# rf_txpa.net
KiCad netlist of a schematic drawn in Altium Designer
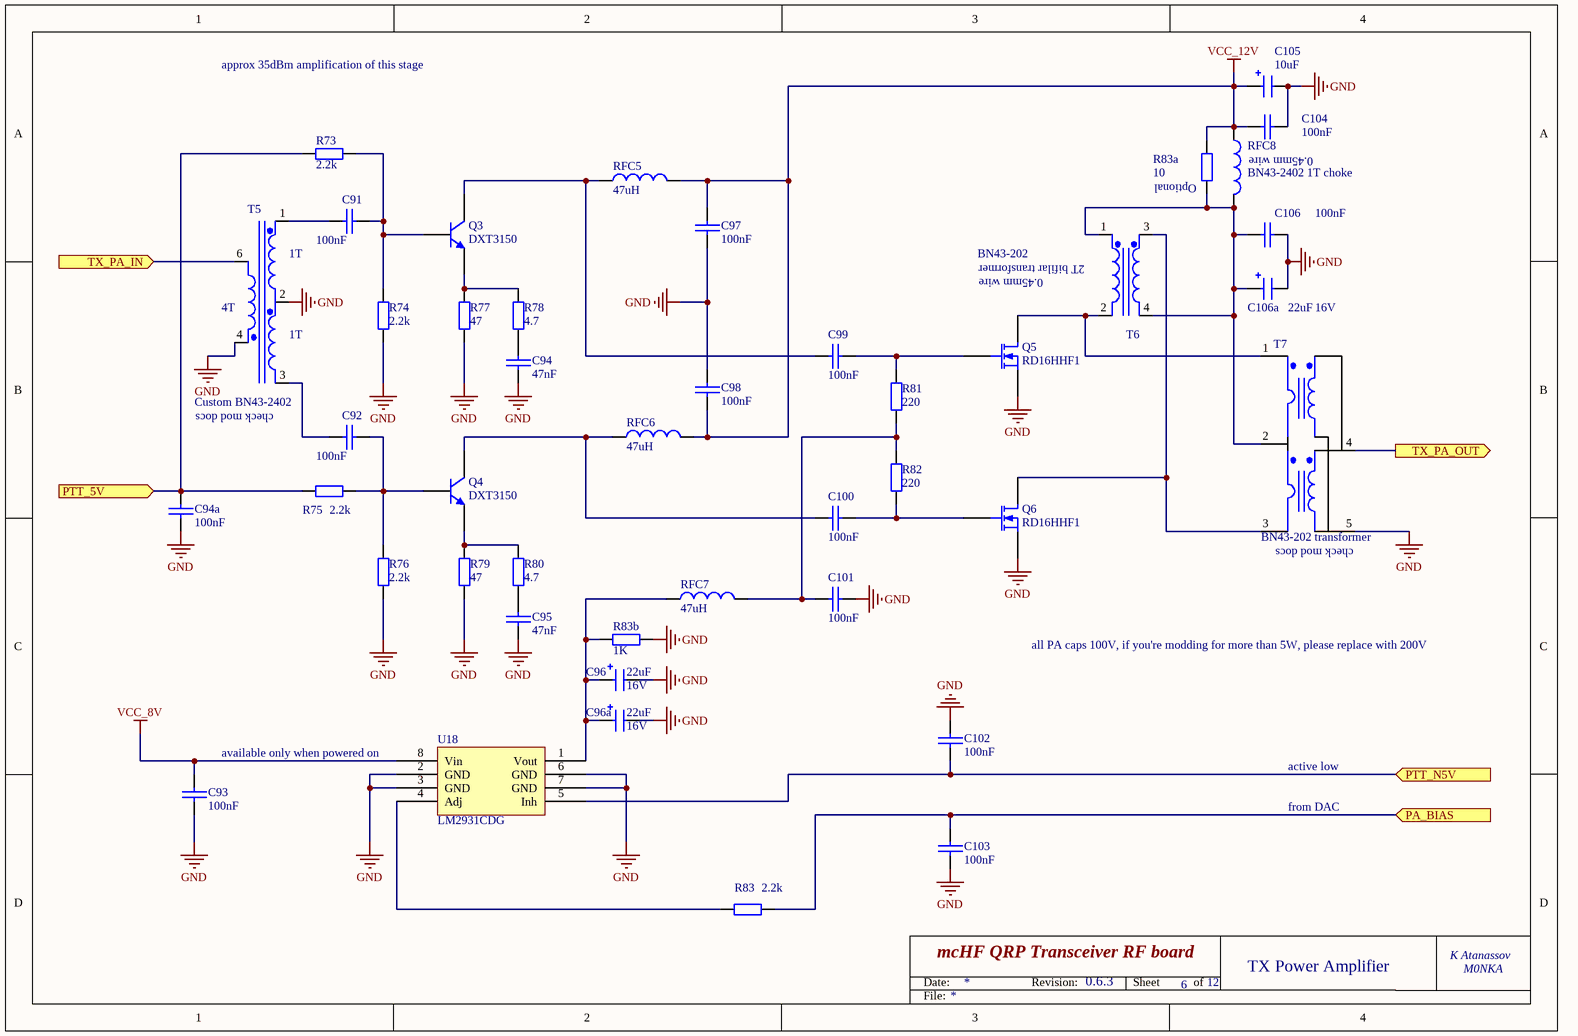
[diagram p0: rf_txpa.SchDoc]

(export (version "E")
  (design (tool "Eeschema 10.0.6"))
  (components
    (comp (ref "C91")
      (value "100nF")
      (footprint "0805-Pro")
      (description "Capacitor")
      (fields (field (name "VOLTAGE") "100V"))
      (libsource (lib "mcHF_rf") (part "CAP"))
    )
    (comp (ref "C92")
      (value "100nF")
      (footprint "0805-Pro")
      (description "Capacitor")
      (fields (field (name "VOLTAGE") "100V"))
      (libsource (lib "mcHF_rf") (part "CAP"))
    )
    (comp (ref "C93")
      (value "100nF")
      (footprint "0805-Pro")
      (description "Capacitor")
      (fields (field (name "VOLTAGE") "100V"))
      (libsource (lib "mcHF_rf") (part "CAP"))
    )
    (comp (ref "C94")
      (value "47nF")
      (footprint "0805-Pro")
      (description "Capacitor")
      (libsource (lib "mcHF_rf") (part "CAP"))
    )
    (comp (ref "C94a")
      (value "100nF")
      (footprint "0805-Pro")
      (description "Capacitor")
      (fields (field (name "VOLTAGE") "100V"))
      (libsource (lib "mcHF_rf") (part "CAP"))
    )
    (comp (ref "C95")
      (value "47nF")
      (footprint "0805-Pro")
      (description "Capacitor")
      (libsource (lib "mcHF_rf") (part "CAP"))
    )
    (comp (ref "C96")
      (value "22uF")
      (footprint "1206_Elec_Cap_N")
      (description "Electrolitic capacitor")
      (fields (field (name "VOLTAGE") "16V"))
      (libsource (lib "mcHF_rf") (part "CAP-POL"))
    )
    (comp (ref "C96a")
      (value "22uF")
      (footprint "1206_Elec_Cap_N")
      (description "Electrolitic capacitor")
      (fields (field (name "VOLTAGE") "16V"))
      (libsource (lib "mcHF_rf") (part "CAP-POL"))
    )
    (comp (ref "C97")
      (value "100nF")
      (footprint "0805-Pro")
      (description "Capacitor")
      (fields (field (name "VOLTAGE") "100V"))
      (libsource (lib "mcHF_rf") (part "CAP"))
    )
    (comp (ref "C98")
      (value "100nF")
      (footprint "0805-Pro")
      (description "Capacitor")
      (fields (field (name "VOLTAGE") "100V"))
      (libsource (lib "mcHF_rf") (part "CAP"))
    )
    (comp (ref "C99")
      (value "100nF")
      (footprint "0805-Pro")
      (description "Capacitor")
      (fields (field (name "VOLTAGE") "100V"))
      (libsource (lib "mcHF_rf") (part "CAP"))
    )
    (comp (ref "C100")
      (value "100nF")
      (footprint "0805-Pro")
      (description "Capacitor")
      (fields (field (name "VOLTAGE") "100V"))
      (libsource (lib "mcHF_rf") (part "CAP"))
    )
    (comp (ref "C101")
      (value "100nF")
      (footprint "0805-Pro")
      (description "Capacitor")
      (fields (field (name "VOLTAGE") "100V"))
      (libsource (lib "mcHF_rf") (part "CAP"))
    )
    (comp (ref "C102")
      (value "100nF")
      (footprint "0805-Pro")
      (description "Capacitor")
      (fields (field (name "VOLTAGE") "100V"))
      (libsource (lib "mcHF_rf") (part "CAP"))
    )
    (comp (ref "C103")
      (value "100nF")
      (footprint "0805-Pro")
      (description "Capacitor")
      (fields (field (name "VOLTAGE") "100V"))
      (libsource (lib "mcHF_rf") (part "CAP"))
    )
    (comp (ref "C104")
      (value "100nF")
      (footprint "0805-Pro")
      (description "Capacitor")
      (fields (field (name "VOLTAGE") "100V"))
      (libsource (lib "mcHF_rf") (part "CAP"))
    )
    (comp (ref "C105")
      (value "10uF")
      (footprint "1206_Elec_Cap_N")
      (description "Electrolitic capacitor")
      (libsource (lib "mcHF_rf") (part "CAP-POL"))
    )
    (comp (ref "C106")
      (value "100nF")
      (footprint "0805-Pro")
      (description "Capacitor")
      (fields (field (name "VOLTAGE") "100V"))
      (libsource (lib "mcHF_rf") (part "CAP"))
    )
    (comp (ref "C106a")
      (value "22uF")
      (footprint "1206_Elec_Cap_N")
      (description "Electrolitic capacitor")
      (fields (field (name "VOLTAGE") "16V"))
      (libsource (lib "mcHF_rf") (part "CAP-POL"))
    )
    (comp (ref "Q3")
      (value "DXT3150")
      (footprint "SOT89L_new")
      (description "BIPOLAR, TRANSISTOR, NPN, SOT-89")
      (libsource (lib "mcHF_rf") (part "DXT3150"))
    )
    (comp (ref "Q4")
      (value "DXT3150")
      (footprint "SOT89L_new")
      (description "BIPOLAR, TRANSISTOR, NPN, SOT-89")
      (libsource (lib "mcHF_rf") (part "DXT3150"))
    )
    (comp (ref "Q5")
      (value "RD16HHF1")
      (footprint "TO-220RF_dual")
      (description "Silicon RF Power MOS FET")
      (libsource (lib "mcHF_rf") (part "RD16HHF1"))
    )
    (comp (ref "Q6")
      (value "RD16HHF1")
      (footprint "TO-220RF_dual")
      (description "Silicon RF Power MOS FET")
      (libsource (lib "mcHF_rf") (part "RD16HHF1"))
    )
    (comp (ref "R73")
      (value "2.2k")
      (footprint "0805-Pro")
      (description "Resistor")
      (libsource (lib "") (part "RES_1"))
    )
    (comp (ref "R74")
      (value "2.2k")
      (footprint "0805-Pro")
      (description "Resistor")
      (libsource (lib "mcHF_rf") (part "RES"))
    )
    (comp (ref "R75")
      (value "2.2k")
      (footprint "0805-Pro")
      (description "Resistor")
      (libsource (lib "") (part "RES_3"))
    )
    (comp (ref "R76")
      (value "2.2k")
      (footprint "0805-Pro")
      (description "Resistor")
      (libsource (lib "mcHF_rf") (part "RES"))
    )
    (comp (ref "R77")
      (value "47")
      (footprint "0805-Pro")
      (description "Resistor")
      (libsource (lib "") (part "RES_2"))
    )
    (comp (ref "R78")
      (value "4.7")
      (footprint "0805-Pro")
      (description "Resistor")
      (libsource (lib "") (part "RES_2"))
    )
    (comp (ref "R79")
      (value "47")
      (footprint "0805-Pro")
      (description "Resistor")
      (libsource (lib "") (part "RES_2"))
    )
    (comp (ref "R80")
      (value "4.7")
      (footprint "0805-Pro")
      (description "Resistor")
      (libsource (lib "") (part "RES_2"))
    )
    (comp (ref "R81")
      (value "220")
      (footprint "0805-Pro")
      (description "Resistor")
      (libsource (lib "") (part "RES_2"))
    )
    (comp (ref "R82")
      (value "220")
      (footprint "0805-Pro")
      (description "Resistor")
      (libsource (lib "") (part "RES_2"))
    )
    (comp (ref "R83")
      (value "2.2k")
      (footprint "0805-Pro")
      (description "Resistor")
      (libsource (lib "") (part "RES_3"))
    )
    (comp (ref "R83a")
      (value "10")
      (footprint "0805-Pro")
      (description "Resistor")
      (libsource (lib "") (part "RES_2"))
    )
    (comp (ref "R83b")
      (value "1K")
      (footprint "0805-Pro")
      (description "Resistor")
      (libsource (lib "") (part "RES_1"))
    )
    (comp (ref "RFC5")
      (value "47uH")
      (footprint "0805-Pro")
      (description "INDUCTOR, SIGNAL LINE, 4.7UH, 1005")
      (libsource (lib "mcHF_rf") (part "TDK-NLV25T"))
    )
    (comp (ref "RFC6")
      (value "47uH")
      (footprint "0805-Pro")
      (description "INDUCTOR, SIGNAL LINE, 4.7UH, 1005")
      (libsource (lib "mcHF_rf") (part "TDK-NLV25T"))
    )
    (comp (ref "RFC7")
      (value "47uH")
      (footprint "0805-Pro")
      (description "INDUCTOR, SIGNAL LINE, 4.7UH, 1005")
      (libsource (lib "mcHF_rf") (part "TDK-NLV25T"))
    )
    (comp (ref "RFC8")
      (value "BN43-2402 1T choke")
      (footprint "F_Bead")
      (description "BN43-2402 1t choke")
      (libsource (lib "mcHF_rf") (part "FER_BEAD"))
    )
    (comp (ref "T5")
      (value "Custom BN43-2402")
      (footprint "SOP5_NEW1thr")
      (description "Transformer 4:1")
      (libsource (lib "mcHF_rf") (part "CX2074NL"))
    )
    (comp (ref "T6")
      (value "BN43-202")
      (footprint "PA_TRM_b1")
      (description "BN43-202 bifilar transformer")
      (libsource (lib "mcHF_rf") (part "PA_TR_b"))
    )
    (comp (ref "T7")
      (value "BN43-202 transformer")
      (footprint "PA_TRM_4m")
      (description "BN43-202 2:3 transformer")
      (libsource (lib "mcHF_rf") (part "PA_TR_4m"))
    )
    (comp (ref "U18")
      (value "LM2931CDG")
      (footprint "SO-8-Pro")
      (description "100 mA, Adjustable Output,  LDO Voltage Regulator with  60 V Load Dump Protection")
      (libsource (lib "mcHF_rf") (part "LM2931CDG"))
    )
  )
  (nets
    (net (code "1") (name "/PA_BIAS") (class "Default")
      (node (ref "C103") (pin "1") (pinfunction "1_1") (pintype "passive"))
      (node (ref "R83") (pin "2") (pinfunction "2_2") (pintype "passive"))
    )
    (net (code "2") (name "/PTT_5V") (class "Default")
      (node (ref "C94a") (pin "1") (pinfunction "1_1") (pintype "passive"))
      (node (ref "R73") (pin "2") (pinfunction "2_2") (pintype "passive"))
      (node (ref "R75") (pin "1") (pinfunction "1_1") (pintype "passive"))
    )
    (net (code "3") (name "/PTT_N5V") (class "Default")
      (node (ref "C102") (pin "2") (pinfunction "2_2") (pintype "passive"))
      (node (ref "U18") (pin "5") (pinfunction "Inh_5") (pintype "passive"))
    )
    (net (code "4") (name "/TX_PA_IN") (class "Default")
      (node (ref "T5") (pin "6") (pinfunction "Pri+_6") (pintype "passive"))
    )
    (net (code "5") (name "/TX_PA_OUT") (class "Default")
      (node (ref "T7") (pin "4") (pinfunction "Sec+_4") (pintype "passive"))
    )
    (net (code "6") (name "GND") (class "Default")
      (node (ref "C101") (pin "1") (pinfunction "1_1") (pintype "passive"))
      (node (ref "C102") (pin "1") (pinfunction "1_1") (pintype "passive"))
      (node (ref "C103") (pin "2") (pinfunction "2_2") (pintype "passive"))
      (node (ref "C104") (pin "1") (pinfunction "1_1") (pintype "passive"))
      (node (ref "C105") (pin "2") (pinfunction "2_2") (pintype "passive"))
      (node (ref "C106") (pin "1") (pinfunction "1_1") (pintype "passive"))
      (node (ref "C106a") (pin "2") (pinfunction "2_2") (pintype "passive"))
      (node (ref "C93") (pin "2") (pinfunction "2_2") (pintype "passive"))
      (node (ref "C94") (pin "2") (pinfunction "2_2") (pintype "passive"))
      (node (ref "C94a") (pin "2") (pinfunction "2_2") (pintype "passive"))
      (node (ref "C95") (pin "2") (pinfunction "2_2") (pintype "passive"))
      (node (ref "C96") (pin "2") (pinfunction "2_2") (pintype "passive"))
      (node (ref "C96a") (pin "2") (pinfunction "2_2") (pintype "passive"))
      (node (ref "C97") (pin "2") (pinfunction "2_2") (pintype "passive"))
      (node (ref "C98") (pin "1") (pinfunction "1_1") (pintype "passive"))
      (node (ref "Q5") (pin "2") (pinfunction "S_2") (pintype "passive"))
      (node (ref "Q6") (pin "2") (pinfunction "S_2") (pintype "passive"))
      (node (ref "R74") (pin "2") (pinfunction "2_2") (pintype "passive"))
      (node (ref "R76") (pin "2") (pinfunction "2_2") (pintype "passive"))
      (node (ref "R77") (pin "1") (pinfunction "1_1") (pintype "passive"))
      (node (ref "R79") (pin "1") (pinfunction "1_1") (pintype "passive"))
      (node (ref "R83b") (pin "1") (pinfunction "1_1") (pintype "passive"))
      (node (ref "T5") (pin "2") (pinfunction "SecCmn_2") (pintype "passive"))
      (node (ref "T5") (pin "4") (pinfunction "Pri-_4") (pintype "passive"))
      (node (ref "T7") (pin "5") (pinfunction "Sec-_5") (pintype "passive"))
      (node (ref "U18") (pin "2") (pinfunction "GND_2") (pintype "passive"))
      (node (ref "U18") (pin "3") (pinfunction "GND_3") (pintype "passive"))
      (node (ref "U18") (pin "6") (pinfunction "GND_6") (pintype "passive"))
      (node (ref "U18") (pin "7") (pinfunction "GND_7") (pintype "passive"))
    )
    (net (code "7") (name "Net-(C94-Pad1)") (class "Default")
      (node (ref "C94") (pin "1") (pinfunction "1_1") (pintype "passive"))
      (node (ref "R78") (pin "1") (pinfunction "1_1") (pintype "passive"))
    )
    (net (code "8") (name "Net-(C95-Pad1)") (class "Default")
      (node (ref "C95") (pin "1") (pinfunction "1_1") (pintype "passive"))
      (node (ref "R80") (pin "1") (pinfunction "1_1") (pintype "passive"))
    )
    (net (code "9") (name "Net-(C101-Pad2)") (class "Default")
      (node (ref "C101") (pin "2") (pinfunction "2_2") (pintype "passive"))
      (node (ref "R81") (pin "1") (pinfunction "1_1") (pintype "passive"))
      (node (ref "R82") (pin "2") (pinfunction "2_2") (pintype "passive"))
      (node (ref "RFC7") (pin "2") (pinfunction "2_2") (pintype "passive"))
    )
    (net (code "10") (name "Net-(Q3-B)") (class "Default")
      (node (ref "C91") (pin "1") (pinfunction "1_1") (pintype "passive"))
      (node (ref "Q3") (pin "1") (pinfunction "B_1") (pintype "passive"))
      (node (ref "R73") (pin "1") (pinfunction "1_1") (pintype "passive"))
      (node (ref "R74") (pin "1") (pinfunction "1_1") (pintype "passive"))
    )
    (net (code "11") (name "Net-(Q3-C)") (class "Default")
      (node (ref "C99") (pin "2") (pinfunction "2_2") (pintype "passive"))
      (node (ref "Q3") (pin "2") (pinfunction "C_2") (pintype "passive"))
      (node (ref "RFC5") (pin "1") (pinfunction "1_1") (pintype "passive"))
    )
    (net (code "12") (name "Net-(Q3-E)") (class "Default")
      (node (ref "Q3") (pin "3") (pinfunction "E_3") (pintype "passive"))
      (node (ref "R77") (pin "2") (pinfunction "2_2") (pintype "passive"))
      (node (ref "R78") (pin "2") (pinfunction "2_2") (pintype "passive"))
    )
    (net (code "13") (name "Net-(Q4-B)") (class "Default")
      (node (ref "C92") (pin "1") (pinfunction "1_1") (pintype "passive"))
      (node (ref "Q4") (pin "1") (pinfunction "B_1") (pintype "passive"))
      (node (ref "R75") (pin "2") (pinfunction "2_2") (pintype "passive"))
      (node (ref "R76") (pin "1") (pinfunction "1_1") (pintype "passive"))
    )
    (net (code "14") (name "Net-(Q4-C)") (class "Default")
      (node (ref "C100") (pin "2") (pinfunction "2_2") (pintype "passive"))
      (node (ref "Q4") (pin "2") (pinfunction "C_2") (pintype "passive"))
      (node (ref "RFC6") (pin "1") (pinfunction "1_1") (pintype "passive"))
    )
    (net (code "15") (name "Net-(Q4-E)") (class "Default")
      (node (ref "Q4") (pin "3") (pinfunction "E_3") (pintype "passive"))
      (node (ref "R79") (pin "2") (pinfunction "2_2") (pintype "passive"))
      (node (ref "R80") (pin "2") (pinfunction "2_2") (pintype "passive"))
    )
    (net (code "16") (name "Net-(Q5-D)") (class "Default")
      (node (ref "Q5") (pin "3") (pinfunction "D_3") (pintype "passive"))
      (node (ref "T6") (pin "2") (pinfunction "Pri-_2") (pintype "passive"))
      (node (ref "T7") (pin "1") (pinfunction "Pri_0_deg_1") (pintype "passive"))
    )
    (net (code "17") (name "Net-(Q5-G)") (class "Default")
      (node (ref "C99") (pin "1") (pinfunction "1_1") (pintype "passive"))
      (node (ref "Q5") (pin "1") (pinfunction "G_1") (pintype "passive"))
      (node (ref "R81") (pin "2") (pinfunction "2_2") (pintype "passive"))
    )
    (net (code "18") (name "Net-(Q6-D)") (class "Default")
      (node (ref "Q6") (pin "3") (pinfunction "D_3") (pintype "passive"))
      (node (ref "T6") (pin "3") (pinfunction "Sec+_3") (pintype "passive"))
      (node (ref "T7") (pin "3") (pinfunction "Pri_180_deg_3") (pintype "passive"))
    )
    (net (code "19") (name "Net-(Q6-G)") (class "Default")
      (node (ref "C100") (pin "1") (pinfunction "1_1") (pintype "passive"))
      (node (ref "Q6") (pin "1") (pinfunction "G_1") (pintype "passive"))
      (node (ref "R82") (pin "1") (pinfunction "1_1") (pintype "passive"))
    )
    (net (code "20") (name "Net-(T5-Sec0)") (class "Default")
      (node (ref "C91") (pin "2") (pinfunction "2_2") (pintype "passive"))
      (node (ref "T5") (pin "1") (pinfunction "Sec0_1") (pintype "passive"))
    )
    (net (code "21") (name "Net-(T5-Sec180)") (class "Default")
      (node (ref "C92") (pin "2") (pinfunction "2_2") (pintype "passive"))
      (node (ref "T5") (pin "3") (pinfunction "Sec180_3") (pintype "passive"))
    )
    (net (code "22") (name "Net-(T6-Pri+)") (class "Default")
      (node (ref "C106") (pin "2") (pinfunction "2_2") (pintype "passive"))
      (node (ref "C106a") (pin "1") (pinfunction "1_1") (pintype "passive"))
      (node (ref "R83a") (pin "1") (pinfunction "1_1") (pintype "passive"))
      (node (ref "RFC8") (pin "2") (pinfunction "2_2") (pintype "passive"))
      (node (ref "T6") (pin "1") (pinfunction "Pri+_1") (pintype "passive"))
      (node (ref "T6") (pin "4") (pinfunction "Sec-_4") (pintype "passive"))
      (node (ref "T7") (pin "2") (pinfunction "Pri_Common_2") (pintype "passive"))
    )
    (net (code "23") (name "Net-(U18-Adj)") (class "Default")
      (node (ref "R83") (pin "1") (pinfunction "1_1") (pintype "passive"))
      (node (ref "U18") (pin "4") (pinfunction "Adj_4") (pintype "passive"))
    )
    (net (code "24") (name "Net-(U18-Vout)") (class "Default")
      (node (ref "C96") (pin "1") (pinfunction "1_1") (pintype "passive"))
      (node (ref "C96a") (pin "1") (pinfunction "1_1") (pintype "passive"))
      (node (ref "R83b") (pin "2") (pinfunction "2_2") (pintype "passive"))
      (node (ref "RFC7") (pin "1") (pinfunction "1_1") (pintype "passive"))
      (node (ref "U18") (pin "1") (pinfunction "Vout_1") (pintype "passive"))
    )
    (net (code "25") (name "VCC_8V") (class "Default")
      (node (ref "C93") (pin "1") (pinfunction "1_1") (pintype "passive"))
      (node (ref "U18") (pin "8") (pinfunction "Vin_8") (pintype "passive"))
    )
    (net (code "26") (name "VCC_12V") (class "Default")
      (node (ref "C104") (pin "2") (pinfunction "2_2") (pintype "passive"))
      (node (ref "C105") (pin "1") (pinfunction "1_1") (pintype "passive"))
      (node (ref "C97") (pin "1") (pinfunction "1_1") (pintype "passive"))
      (node (ref "C98") (pin "2") (pinfunction "2_2") (pintype "passive"))
      (node (ref "R83a") (pin "2") (pinfunction "2_2") (pintype "passive"))
      (node (ref "RFC5") (pin "2") (pinfunction "2_2") (pintype "passive"))
      (node (ref "RFC6") (pin "2") (pinfunction "2_2") (pintype "passive"))
      (node (ref "RFC8") (pin "1") (pinfunction "1_1") (pintype "passive"))
    )
  )
)
